# Physics_module_mount_v1_1.net
KiCad netlist of a schematic drawn in EAGLE
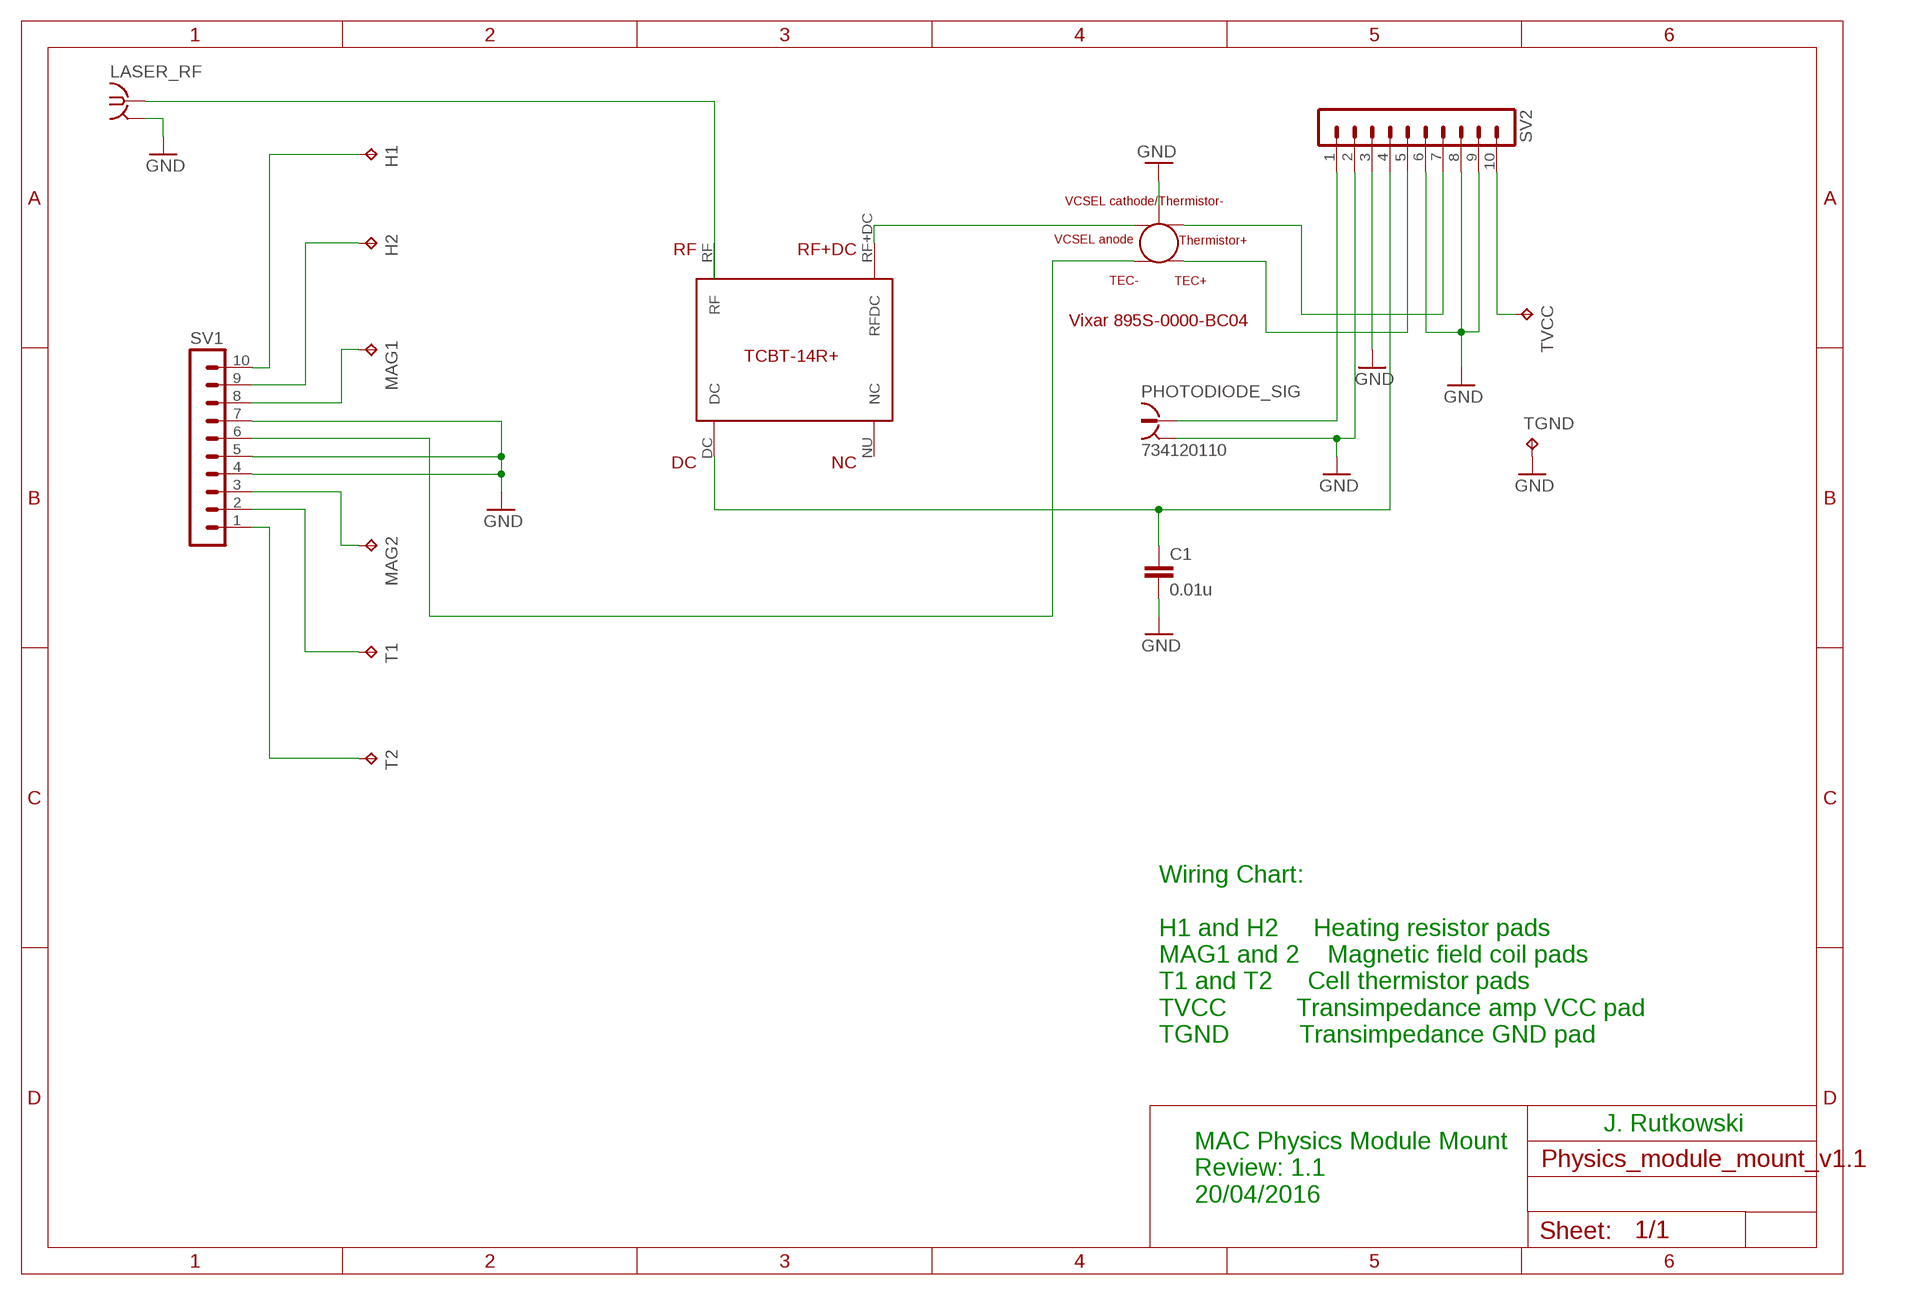
[diagram p0: schematic, sheet 1]

(export (version "E")
  (design (tool "Eeschema 10.0.6"))
  (components
    (comp (ref "C1")
      (value "0.01u")
      (footprint "eagle-import:C0603K")
      (libsource (lib "eagle-import") (part "C-EUC0603K"))
    )
    (comp (ref "H1")
      (value "TPPAD1-13")
      (footprint "eagle-import:P1-13")
      (libsource (lib "eagle-import") (part "TPPAD1-13"))
    )
    (comp (ref "H2")
      (value "TPPAD1-13")
      (footprint "eagle-import:P1-13")
      (libsource (lib "eagle-import") (part "TPPAD1-13"))
    )
    (comp (ref "LASER_RF")
      (value "SMA-142-0711-871/876")
      (footprint "eagle-import:J502-ND-142-0711-871_876")
      (fields (field (name "MF") "JOHNSON COMPONENTS") (field (name "MPN") "142-0711-871"))
      (libsource (lib "eagle-import") (part "SMA-142-0711-871/876"))
    )
    (comp (ref "MAG1")
      (value "TPPAD1-13")
      (footprint "eagle-import:P1-13")
      (libsource (lib "eagle-import") (part "TPPAD1-13"))
    )
    (comp (ref "MAG2")
      (value "TPPAD1-13")
      (footprint "eagle-import:P1-13")
      (libsource (lib "eagle-import") (part "TPPAD1-13"))
    )
    (comp (ref "PHOTODIODE_SIG")
      (value "734120110")
      (footprint "eagle-import:734120110")
      (libsource (lib "eagle-import") (part "734120110"))
    )
    (comp (ref "Q1")
      (value "VIXAR_895NM_VCSEL_TO46_6PIN")
      (footprint "eagle-import:TO45_THT_SMD")
      (libsource (lib "eagle-import") (part "VIXAR_895NM_VCSEL_TO46_6PIN"))
    )
    (comp (ref "SV1")
      (value "MA10-1")
      (footprint "eagle-import:MA10-1")
      (libsource (lib "eagle-import") (part "MA10-1"))
    )
    (comp (ref "SV2")
      (value "MA10-1")
      (footprint "eagle-import:MA10-1")
      (libsource (lib "eagle-import") (part "MA10-1"))
    )
    (comp (ref "T1")
      (value "TPPAD1-13")
      (footprint "eagle-import:P1-13")
      (libsource (lib "eagle-import") (part "TPPAD1-13"))
    )
    (comp (ref "T2")
      (value "TPPAD1-13")
      (footprint "eagle-import:P1-13")
      (libsource (lib "eagle-import") (part "TPPAD1-13"))
    )
    (comp (ref "TGND")
      (value "TPPAD1-13")
      (footprint "eagle-import:P1-13")
      (libsource (lib "eagle-import") (part "TPPAD1-13"))
    )
    (comp (ref "TVCC")
      (value "TPPAD1-13")
      (footprint "eagle-import:P1-13")
      (libsource (lib "eagle-import") (part "TPPAD1-13"))
    )
    (comp (ref "U1")
      (value "TCBT-14+")
      (footprint "eagle-import:TCBT_14_PAC")
      (libsource (lib "eagle-import") (part "TCBT-14+"))
    )
  )
  (nets
    (net (code "1") (name "GND") (class "Default")
      (node (ref "C1") (pin "2") (pinfunction "2_2") (pintype "passive"))
      (node (ref "LASER_RF") (pin "G@1") (pinfunction "2_G@1") (pintype "passive"))
      (node (ref "LASER_RF") (pin "G@2") (pinfunction "2_G@2") (pintype "passive"))
      (node (ref "LASER_RF") (pin "G@3") (pinfunction "2_G@3") (pintype "passive"))
      (node (ref "LASER_RF") (pin "G@4") (pinfunction "2_G@4") (pintype "passive"))
      (node (ref "PHOTODIODE_SIG") (pin "S@1") (pinfunction "2_S@1") (pintype "passive"))
      (node (ref "PHOTODIODE_SIG") (pin "S@2") (pinfunction "2_S@2") (pintype "passive"))
      (node (ref "PHOTODIODE_SIG") (pin "S@3") (pinfunction "2_S@3") (pintype "passive"))
      (node (ref "Q1") (pin "LD_CATHODE_THERM") (pinfunction "VCSEL_CATHODE/THERMISTOR-/CASE_LD_CATHODE_THERM") (pintype "passive"))
      (node (ref "SV1") (pin "4") (pinfunction "4_4") (pintype "passive"))
      (node (ref "SV1") (pin "5") (pinfunction "5_5") (pintype "passive"))
      (node (ref "SV1") (pin "7") (pinfunction "7_7") (pintype "passive"))
      (node (ref "SV2") (pin "2") (pinfunction "2_2") (pintype "passive"))
      (node (ref "SV2") (pin "3") (pinfunction "3_3") (pintype "passive"))
      (node (ref "SV2") (pin "6") (pinfunction "6_6") (pintype "passive"))
      (node (ref "SV2") (pin "8") (pinfunction "8_8") (pintype "passive"))
      (node (ref "SV2") (pin "9") (pinfunction "9_9") (pintype "passive"))
      (node (ref "TGND") (pin "TP") (pinfunction "TP_TP") (pintype "input"))
    )
    (net (code "2") (name "Net-(C1-Pad1)") (class "Default")
      (node (ref "C1") (pin "1") (pinfunction "1_1") (pintype "passive"))
      (node (ref "SV2") (pin "4") (pinfunction "4_4") (pintype "passive"))
      (node (ref "U1") (pin "DC") (pinfunction "DC_DC") (pintype "bidirectional"))
    )
    (net (code "3") (name "Net-(H1-PadTP)") (class "Default")
      (node (ref "H1") (pin "TP") (pinfunction "TP_TP") (pintype "input"))
      (node (ref "SV1") (pin "10") (pinfunction "10_10") (pintype "passive"))
    )
    (net (code "4") (name "Net-(H2-PadTP)") (class "Default")
      (node (ref "H2") (pin "TP") (pinfunction "TP_TP") (pintype "input"))
      (node (ref "SV1") (pin "9") (pinfunction "9_9") (pintype "passive"))
    )
    (net (code "5") (name "Net-(LASER_RF-Pad1)") (class "Default")
      (node (ref "LASER_RF") (pin "1") (pinfunction "1_1") (pintype "passive"))
      (node (ref "U1") (pin "RF") (pinfunction "RF_RF") (pintype "bidirectional"))
    )
    (net (code "6") (name "Net-(MAG1-PadTP)") (class "Default")
      (node (ref "MAG1") (pin "TP") (pinfunction "TP_TP") (pintype "input"))
      (node (ref "SV1") (pin "8") (pinfunction "8_8") (pintype "passive"))
    )
    (net (code "7") (name "Net-(MAG2-PadTP)") (class "Default")
      (node (ref "MAG2") (pin "TP") (pinfunction "TP_TP") (pintype "input"))
      (node (ref "SV1") (pin "3") (pinfunction "3_3") (pintype "passive"))
    )
    (net (code "8") (name "Net-(PHOTODIODE_SIG-Pad1)") (class "Default")
      (node (ref "PHOTODIODE_SIG") (pin "1") (pinfunction "1_1") (pintype "passive"))
      (node (ref "SV2") (pin "1") (pinfunction "1_1") (pintype "passive"))
    )
    (net (code "9") (name "Net-(Q1-PadTEC+)") (class "Default")
      (node (ref "Q1") (pin "TEC+") (pinfunction "TEC+_TEC+") (pintype "passive"))
      (node (ref "SV2") (pin "5") (pinfunction "5_5") (pintype "passive"))
    )
    (net (code "10") (name "Net-(Q1-PadTEC-)") (class "Default")
      (node (ref "Q1") (pin "TEC-") (pinfunction "TEC-_TEC-") (pintype "passive"))
      (node (ref "SV1") (pin "6") (pinfunction "6_6") (pintype "passive"))
    )
    (net (code "11") (name "Net-(Q1-THERMISTOR+)") (class "Default")
      (node (ref "Q1") (pin "THERMISTOR") (pinfunction "THERMISTOR+_THERMISTOR") (pintype "passive"))
      (node (ref "SV2") (pin "7") (pinfunction "7_7") (pintype "passive"))
    )
    (net (code "12") (name "Net-(Q1-VCSEL_ANODE)") (class "Default")
      (node (ref "Q1") (pin "LD_ANODE") (pinfunction "VCSEL_ANODE_LD_ANODE") (pintype "passive"))
      (node (ref "U1") (pin "RF+DC") (pinfunction "RFDC_RF+DC") (pintype "bidirectional"))
    )
    (net (code "13") (name "Net-(SV1-Pad1)") (class "Default")
      (node (ref "SV1") (pin "1") (pinfunction "1_1") (pintype "passive"))
      (node (ref "T2") (pin "TP") (pinfunction "TP_TP") (pintype "input"))
    )
    (net (code "14") (name "Net-(SV1-Pad2)") (class "Default")
      (node (ref "SV1") (pin "2") (pinfunction "2_2") (pintype "passive"))
      (node (ref "T1") (pin "TP") (pinfunction "TP_TP") (pintype "input"))
    )
    (net (code "15") (name "Net-(SV2-Pad10)") (class "Default")
      (node (ref "SV2") (pin "10") (pinfunction "10_10") (pintype "passive"))
      (node (ref "TVCC") (pin "TP") (pinfunction "TP_TP") (pintype "input"))
    )
    (net (code "16") (name "unconnected-(U1-NC-PadNU)") (class "Default")
      (node (ref "U1") (pin "NU") (pinfunction "NC_NU") (pintype "bidirectional"))
    )
  )
)
